# Sensors.net
KiCad netlist of a schematic drawn in Altium Designer
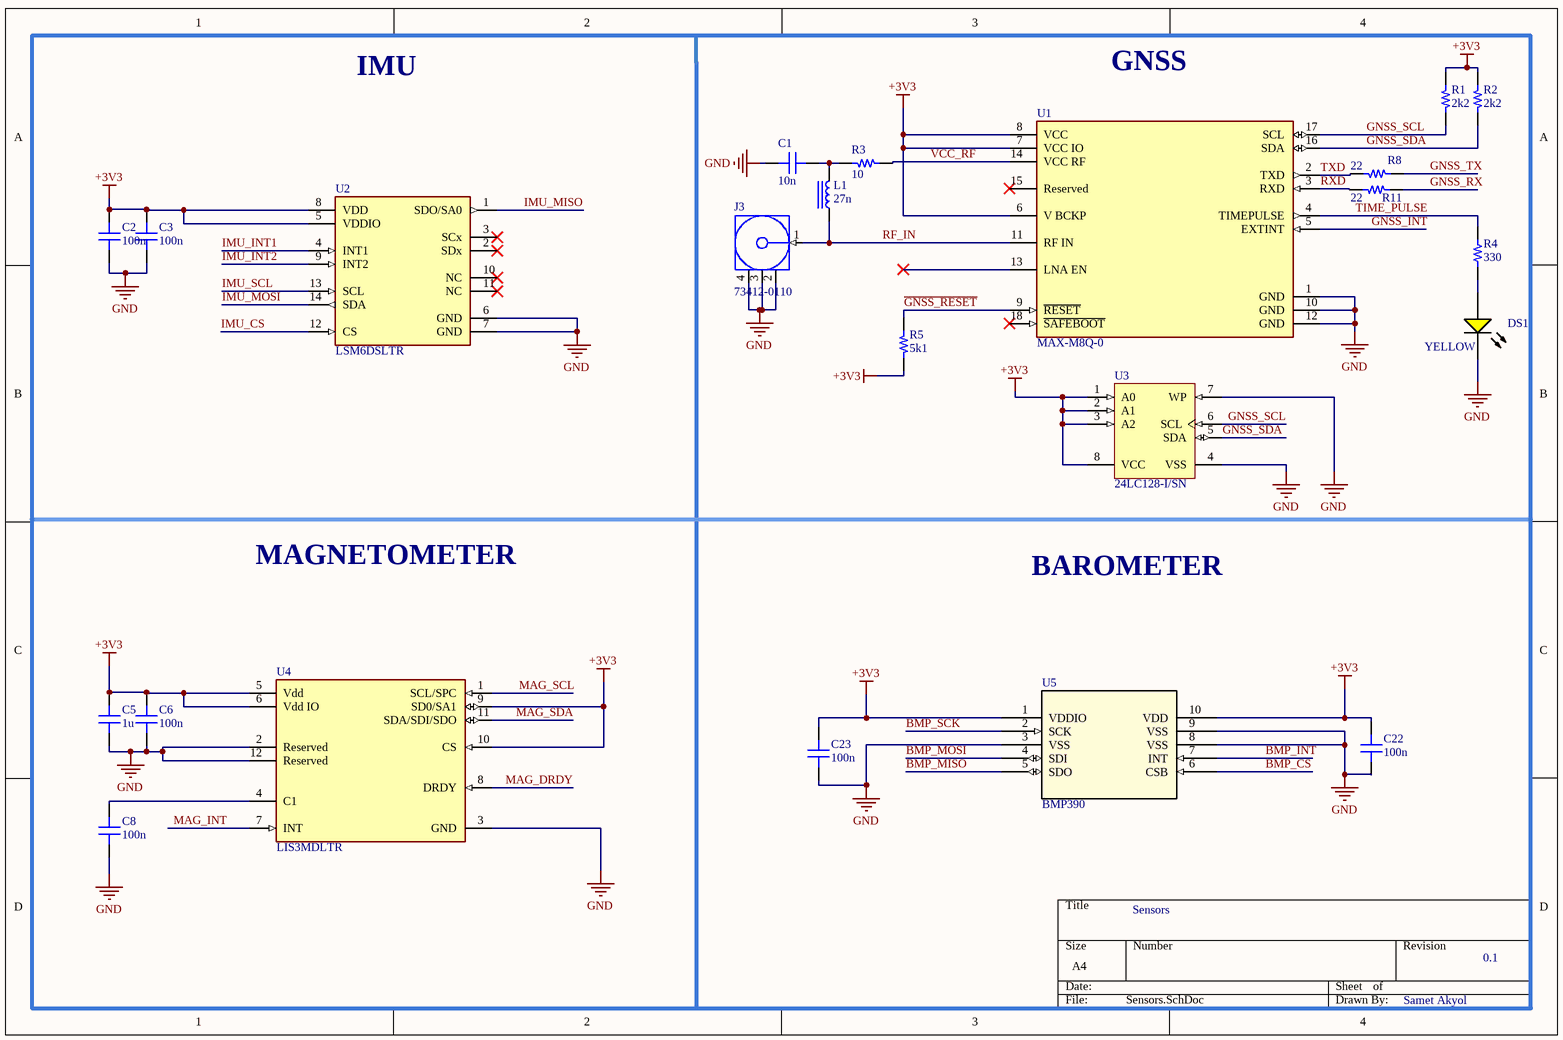
[diagram p0: Sensors.SchDoc]

(export (version "E")
  (design (tool "Eeschema 10.0.6"))
  (components
    (comp (ref "C1")
      (value "10n")
      (footprint "CAP 0402_1005")
      (description "CAP CER 150PF 50V NP0 0402")
      (fields (field (name "PART NUMBER") "C0402C151F5GAC7867") (field (name "MANUFACTURER") "KEMET"))
      (libsource (lib "Celestial Altium Library - altium_library") (part "Capacitor"))
    )
    (comp (ref "C2")
      (value "100n")
      (footprint "CAP 0402_1005")
      (description "CAP CER 0.1UF 10V X7R 0402")
      (fields
        (field (name "PART NUMBER") "MD0402BB104K100NGHT-EM")
        (field (name "MANUFACTURER") "Knowles Novacap")
      )
      (libsource (lib "Celestial Altium Library - altium_library") (part "Capacitor"))
    )
    (comp (ref "C3")
      (value "100n")
      (footprint "CAP 0402_1005")
      (description "CAP CER 0.1UF 10V X7R 0402")
      (fields
        (field (name "PART NUMBER") "MD0402BB104K100NGHT-EM")
        (field (name "MANUFACTURER") "Knowles Novacap")
      )
      (libsource (lib "Celestial Altium Library - altium_library") (part "Capacitor"))
    )
    (comp (ref "C5")
      (value "1u")
      (footprint "CAP 0402_1005")
      (description "CAP CER 0.1UF 10V X7R 0402")
      (fields
        (field (name "PART NUMBER") "MD0402BB104K100NGHT-EM")
        (field (name "MANUFACTURER") "Knowles Novacap")
      )
      (libsource (lib "Celestial Altium Library - altium_library") (part "Capacitor"))
    )
    (comp (ref "C6")
      (value "100n")
      (footprint "CAP 0402_1005")
      (description "CAP CER 0.1UF 10V X7R 0402")
      (fields
        (field (name "PART NUMBER") "MD0402BB104K100NGHT-EM")
        (field (name "MANUFACTURER") "Knowles Novacap")
      )
      (libsource (lib "Celestial Altium Library - altium_library") (part "Capacitor"))
    )
    (comp (ref "C8")
      (value "100n")
      (footprint "CAP 0402_1005")
      (description "CAP CER 0.1UF 10V X7R 0402")
      (fields
        (field (name "PART NUMBER") "MD0402BB104K100NGHT-EM")
        (field (name "MANUFACTURER") "Knowles Novacap")
      )
      (libsource (lib "Celestial Altium Library - altium_library") (part "Capacitor"))
    )
    (comp (ref "C22")
      (value "100n")
      (footprint "CAP 0402_1005")
      (description "CAP CER 0.1UF 10V X7R 0402")
      (fields
        (field (name "PART NUMBER") "MD0402BB104K100NGHT-EM")
        (field (name "MANUFACTURER") "Knowles Novacap")
      )
      (libsource (lib "Celestial Altium Library - altium_library") (part "Capacitor"))
    )
    (comp (ref "C23")
      (value "100n")
      (footprint "CAP 0402_1005")
      (description "CAP CER 0.1UF 10V X7R 0402")
      (fields
        (field (name "PART NUMBER") "MD0402BB104K100NGHT-EM")
        (field (name "MANUFACTURER") "Knowles Novacap")
      )
      (libsource (lib "Celestial Altium Library - altium_library") (part "Capacitor"))
    )
    (comp (ref "DS1")
      (value "YELLOW")
      (footprint "VISH-TLMY1000_V")
      (description "Low Current LED, 40 mW, -40 to 100 degC, 2-Pin SMD, RoHS, Tape and Reel")
      (fields (field (name "MANUFACTURER") "Vishay"))
      (libsource (lib "Altium Content Vault") (part "LED-YELLOW-AK-2"))
    )
    (comp (ref "J3")
      (value "73412-0110")
      (footprint "MOLX-73412-0110_V")
      (description "MCRF, PCB Vertical Jack Receptacle, 50 Ohm, 4-Pin SMD, RoHS, Tape and Reel")
      (libsource (lib "Altium Content Vault") (part "MOLX-73412-0110"))
    )
    (comp (ref "L1")
      (value "27n")
      (footprint "IND 0402_1005 RF WW")
      (description "FIXED IND 160NH 480MA 0.33OHM SM")
      (fields
        (field (name "PART NUMBER") "LQW15CNR16J00D")
        (field (name "MANUFACTURER") "Murata Electronics")
      )
      (libsource (lib "Celestial Altium Library - altium_library") (part "Inductor"))
    )
    (comp (ref "R1")
      (value "2k2")
      (footprint "RES 0402_1005")
      (description "RES 249K OHM 0.1% 1/10W 0402")
      (fields
        (field (name "PART NUMBER") "RP73PF1E249KBTD")
        (field (name "MANUFACTURER") "TE Connectivity Passive Product")
      )
      (libsource (lib "Celestial Altium Library - altium_library") (part "Resistor"))
    )
    (comp (ref "R2")
      (value "2k2")
      (footprint "RES 0402_1005")
      (description "RES 249K OHM 0.1% 1/10W 0402")
      (fields
        (field (name "PART NUMBER") "RP73PF1E249KBTD")
        (field (name "MANUFACTURER") "TE Connectivity Passive Product")
      )
      (libsource (lib "Celestial Altium Library - altium_library") (part "Resistor"))
    )
    (comp (ref "R3")
      (value "10")
      (footprint "RES 0402_1005")
      (description "RES 249K OHM 0.1% 1/10W 0402")
      (fields
        (field (name "PART NUMBER") "RP73PF1E249KBTD")
        (field (name "MANUFACTURER") "TE Connectivity Passive Product")
      )
      (libsource (lib "Celestial Altium Library - altium_library") (part "Resistor"))
    )
    (comp (ref "R4")
      (value "330")
      (footprint "RES 0603_1608")
      (description "RES SMD 330 OHM 1% 1/5W 0603")
      (fields
        (field (name "PART NUMBER") "CRGH0603F330R")
        (field (name "MANUFACTURER") "TE Connectivity Passive Product")
      )
      (libsource (lib "Celestial Altium Library - altium_library") (part "Resistor"))
    )
    (comp (ref "R5")
      (value "5k1")
      (footprint "RES 0402_1005")
      (description "RES 249K OHM 0.1% 1/10W 0402")
      (fields
        (field (name "PART NUMBER") "RP73PF1E249KBTD")
        (field (name "MANUFACTURER") "TE Connectivity Passive Product")
      )
      (libsource (lib "Celestial Altium Library - altium_library") (part "Resistor"))
    )
    (comp (ref "R8")
      (value "22")
      (footprint "RES 0402_1005")
      (description "RES 249K OHM 0.1% 1/10W 0402")
      (fields
        (field (name "PART NUMBER") "RP73PF1E249KBTD")
        (field (name "MANUFACTURER") "TE Connectivity Passive Product")
      )
      (libsource (lib "Celestial Altium Library - altium_library") (part "Resistor"))
    )
    (comp (ref "R11")
      (value "22")
      (footprint "RES 0402_1005")
      (description "RES 249K OHM 0.1% 1/10W 0402")
      (fields
        (field (name "PART NUMBER") "RP73PF1E249KBTD")
        (field (name "MANUFACTURER") "TE Connectivity Passive Product")
      )
      (libsource (lib "Celestial Altium Library - altium_library") (part "Resistor"))
    )
    (comp (ref "U1")
      (value "MAX-M8Q-0")
      (footprint "FP-MAX-M8Q-0-MFG")
      (description "RF RCVR GNSS/GPS 1.575GHZ 18LCC")
      (libsource (lib "Altium Content Vault") (part "3a4eaf80b39255b10f8ea21395ff7da"))
    )
    (comp (ref "U2")
      (value "LSM6DSLTR")
      (footprint "FP-LGA-14L-DM00249496-MFG")
      (description "IMU ACCEL/GYRO I2C/SPI 14LGA")
      (fields
        (field (name "MANUFACTURER") "STMicroelectronics")
        (field (name "OCTOPART") "https://octopart.com/lsm6dsltr-stmicroelectronics-66358193")
      )
      (libsource (lib "Altium Content Vault") (part "4e27e7d1829efda5344af1708d65448"))
    )
    (comp (ref "U3")
      (value "24LC128-I/SN")
      (footprint "SOIC-SN8_M")
      (description "128Kbit, 400kHz, 2.5V, I2C Serial EEPROM, 8-Pin SOIC 150mil, Industrial Temperature")
      (libsource (lib "Altium Content Vault") (part "MEM-SEEPROM-34AA02-IL8"))
    )
    (comp (ref "U4")
      (value "LIS3MDLTR")
      (footprint "FP-VFLGA-12-8365767-MFG")
      (description "SENSOR MR I2C/SPI 12LGA")
      (fields
        (field (name "OCTOPART") "https://octopart.com/lis3mdltr-stmicroelectronics-29403125")
        (field (name "MANUFACTURER") "STMicroelectronics")
      )
      (libsource (lib "Altium Content Vault") (part "41c0331d4207a07573b21020ef49d7d"))
    )
    (comp (ref "U5")
      (value "BMP390")
      (footprint "10LGA_2X2X0p75_BOS-L")
      (description "No Description Available")
      (libsource (lib "BMP390") (part "BMP390"))
    )
  )
  (nets
    (net (code "1") (name "+3V3") (class "Default")
      (node (ref "C2") (pin "2") (pinfunction "2_2") (pintype "passive"))
      (node (ref "C22") (pin "2") (pinfunction "2_2") (pintype "passive"))
      (node (ref "C23") (pin "2") (pinfunction "2_2") (pintype "passive"))
      (node (ref "C3") (pin "2") (pinfunction "2_2") (pintype "passive"))
      (node (ref "C5") (pin "2") (pinfunction "2_2") (pintype "passive"))
      (node (ref "C6") (pin "2") (pinfunction "2_2") (pintype "passive"))
      (node (ref "R1") (pin "2") (pinfunction "2_2") (pintype "passive"))
      (node (ref "R2") (pin "2") (pinfunction "2_2") (pintype "passive"))
      (node (ref "R5") (pin "1") (pinfunction "1_1") (pintype "passive"))
      (node (ref "U1") (pin "6") (pinfunction "V_BCKP_6") (pintype "power_in"))
      (node (ref "U1") (pin "7") (pinfunction "VCC_IO_7") (pintype "power_in"))
      (node (ref "U1") (pin "8") (pinfunction "VCC_8") (pintype "power_in"))
      (node (ref "U2") (pin "5") (pinfunction "VDDIO_5") (pintype "power_in"))
      (node (ref "U2") (pin "8") (pinfunction "VDD_8") (pintype "power_in"))
      (node (ref "U3") (pin "1") (pinfunction "A0_1") (pintype "input"))
      (node (ref "U3") (pin "2") (pinfunction "A1_2") (pintype "input"))
      (node (ref "U3") (pin "3") (pinfunction "A2_3") (pintype "input"))
      (node (ref "U3") (pin "8") (pinfunction "VCC_8") (pintype "power_in"))
      (node (ref "U4") (pin "10") (pinfunction "CS_10") (pintype "input"))
      (node (ref "U4") (pin "5") (pinfunction "Vdd_5") (pintype "power_in"))
      (node (ref "U4") (pin "6") (pinfunction "Vdd_IO_6") (pintype "power_in"))
      (node (ref "U4") (pin "9") (pinfunction "SD0/SA1_9") (pintype "bidirectional"))
      (node (ref "U5") (pin "1") (pinfunction "VDDIO_1") (pintype "power_in"))
      (node (ref "U5") (pin "10") (pinfunction "VDD_10") (pintype "power_in"))
    )
    (net (code "2") (name "/BMP_CS") (class "Default")
      (node (ref "U5") (pin "6") (pinfunction "CSB_6") (pintype "input"))
    )
    (net (code "3") (name "/BMP_INT") (class "Default")
      (node (ref "U5") (pin "7") (pinfunction "INT_7") (pintype "input"))
    )
    (net (code "4") (name "/BMP_MISO") (class "Default")
      (node (ref "U5") (pin "5") (pinfunction "SDO_5") (pintype "bidirectional"))
    )
    (net (code "5") (name "/BMP_MOSI") (class "Default")
      (node (ref "U5") (pin "4") (pinfunction "SDI_4") (pintype "bidirectional"))
    )
    (net (code "6") (name "/BMP_SCK") (class "Default")
      (node (ref "U5") (pin "2") (pinfunction "SCK_2") (pintype "input"))
    )
    (net (code "7") (name "/GNSS_INT") (class "Default")
      (node (ref "U1") (pin "5") (pinfunction "EXTINT_5") (pintype "input"))
    )
    (net (code "8") (name "/GNSS_RX") (class "Default")
      (node (ref "R11") (pin "1") (pinfunction "1_1") (pintype "passive"))
    )
    (net (code "9") (name "/GNSS_SCL") (class "Default")
      (node (ref "R1") (pin "1") (pinfunction "1_1") (pintype "passive"))
      (node (ref "U1") (pin "17") (pinfunction "SCL_17") (pintype "bidirectional"))
      (node (ref "U3") (pin "6") (pinfunction "SCL_6") (pintype "input"))
    )
    (net (code "10") (name "/GNSS_SDA") (class "Default")
      (node (ref "R2") (pin "1") (pinfunction "1_1") (pintype "passive"))
      (node (ref "U1") (pin "16") (pinfunction "SDA_16") (pintype "bidirectional"))
      (node (ref "U3") (pin "5") (pinfunction "SDA_5") (pintype "bidirectional"))
    )
    (net (code "11") (name "/GNSS_TX") (class "Default")
      (node (ref "R8") (pin "1") (pinfunction "1_1") (pintype "passive"))
    )
    (net (code "12") (name "/IMU_CS") (class "Default")
      (node (ref "U2") (pin "12") (pinfunction "CS_12") (pintype "input"))
    )
    (net (code "13") (name "/IMU_INT1") (class "Default")
      (node (ref "U2") (pin "4") (pinfunction "INT1_4") (pintype "input"))
    )
    (net (code "14") (name "/IMU_INT2") (class "Default")
      (node (ref "U2") (pin "9") (pinfunction "INT2_9") (pintype "input"))
    )
    (net (code "15") (name "/IMU_MISO") (class "Default")
      (node (ref "U2") (pin "1") (pinfunction "SDO/SA0_1") (pintype "output"))
    )
    (net (code "16") (name "/IMU_MOSI") (class "Default")
      (node (ref "U2") (pin "14") (pinfunction "SDA_14") (pintype "output"))
    )
    (net (code "17") (name "/IMU_SCL") (class "Default")
      (node (ref "U2") (pin "13") (pinfunction "SCL_13") (pintype "input"))
    )
    (net (code "18") (name "/MAG_DRDY") (class "Default")
      (node (ref "U4") (pin "8") (pinfunction "DRDY_8") (pintype "input"))
    )
    (net (code "19") (name "/MAG_INT") (class "Default")
      (node (ref "U4") (pin "7") (pinfunction "INT_7") (pintype "input"))
    )
    (net (code "20") (name "/MAG_SCL") (class "Default")
      (node (ref "U4") (pin "1") (pinfunction "SCL/SPC_1") (pintype "input"))
    )
    (net (code "21") (name "/MAG_SDA") (class "Default")
      (node (ref "U4") (pin "11") (pinfunction "SDA/SDI/SDO_11") (pintype "bidirectional"))
    )
    (net (code "22") (name "/RF_IN") (class "Default")
      (node (ref "J3") (pin "1") (pinfunction "SIGNAL_1") (pintype "input"))
      (node (ref "L1") (pin "2") (pinfunction "2_2") (pintype "passive"))
      (node (ref "U1") (pin "11") (pinfunction "RF_IN_11") (pintype "passive"))
    )
    (net (code "23") (name "/RXD") (class "Default")
      (node (ref "R11") (pin "2") (pinfunction "2_2") (pintype "passive"))
      (node (ref "U1") (pin "3") (pinfunction "RXD_3") (pintype "input"))
    )
    (net (code "24") (name "/TIME_PULSE") (class "Default")
      (node (ref "R4") (pin "2") (pinfunction "2_2") (pintype "passive"))
      (node (ref "U1") (pin "4") (pinfunction "TIMEPULSE_4") (pintype "output"))
    )
    (net (code "25") (name "/TXD") (class "Default")
      (node (ref "R8") (pin "2") (pinfunction "2_2") (pintype "passive"))
      (node (ref "U1") (pin "2") (pinfunction "TXD_2") (pintype "output"))
    )
    (net (code "26") (name "/VCC_RF") (class "Default")
      (node (ref "R3") (pin "2") (pinfunction "2_2") (pintype "passive"))
      (node (ref "U1") (pin "14") (pinfunction "VCC_RF_14") (pintype "power_in"))
    )
    (net (code "27") (name "/~{GNSS_RESET}") (class "Default")
      (node (ref "R5") (pin "2") (pinfunction "2_2") (pintype "passive"))
      (node (ref "U1") (pin "9") (pinfunction "~{RESET}_9") (pintype "input"))
    )
    (net (code "28") (name "GND") (class "Default")
      (node (ref "C1") (pin "2") (pinfunction "2_2") (pintype "passive"))
      (node (ref "C2") (pin "1") (pinfunction "1_1") (pintype "passive"))
      (node (ref "C22") (pin "1") (pinfunction "1_1") (pintype "passive"))
      (node (ref "C23") (pin "1") (pinfunction "1_1") (pintype "passive"))
      (node (ref "C3") (pin "1") (pinfunction "1_1") (pintype "passive"))
      (node (ref "C5") (pin "1") (pinfunction "1_1") (pintype "passive"))
      (node (ref "C6") (pin "1") (pinfunction "1_1") (pintype "passive"))
      (node (ref "C8") (pin "1") (pinfunction "1_1") (pintype "passive"))
      (node (ref "DS1") (pin "2") (pinfunction "K_2") (pintype "passive"))
      (node (ref "J3") (pin "2") (pinfunction "GND_2") (pintype "power_in"))
      (node (ref "J3") (pin "3") (pinfunction "GND_3") (pintype "power_in"))
      (node (ref "J3") (pin "4") (pinfunction "GND_4") (pintype "power_in"))
      (node (ref "U1") (pin "1") (pinfunction "GND_1") (pintype "power_in"))
      (node (ref "U1") (pin "10") (pinfunction "GND_10") (pintype "power_in"))
      (node (ref "U1") (pin "12") (pinfunction "GND_12") (pintype "power_in"))
      (node (ref "U2") (pin "6") (pinfunction "GND_6") (pintype "power_in"))
      (node (ref "U2") (pin "7") (pinfunction "GND_7") (pintype "power_in"))
      (node (ref "U3") (pin "4") (pinfunction "VSS_4") (pintype "power_in"))
      (node (ref "U3") (pin "7") (pinfunction "WP_7") (pintype "input"))
      (node (ref "U4") (pin "12") (pinfunction "Reserved_12") (pintype "passive"))
      (node (ref "U4") (pin "2") (pinfunction "Reserved_2") (pintype "passive"))
      (node (ref "U4") (pin "3") (pinfunction "GND_3") (pintype "power_in"))
      (node (ref "U5") (pin "3") (pinfunction "VSS_3") (pintype "power_in"))
      (node (ref "U5") (pin "8") (pinfunction "VSS_8") (pintype "power_in"))
      (node (ref "U5") (pin "9") (pinfunction "VSS_9") (pintype "power_in"))
    )
    (net (code "29") (name "Net-(C1-Pad1)") (class "Default")
      (node (ref "C1") (pin "1") (pinfunction "1_1") (pintype "passive"))
      (node (ref "L1") (pin "1") (pinfunction "1_1") (pintype "passive"))
      (node (ref "R3") (pin "1") (pinfunction "1_1") (pintype "passive"))
    )
    (net (code "30") (name "Net-(DS1-A)") (class "Default")
      (node (ref "DS1") (pin "1") (pinfunction "A_1") (pintype "passive"))
      (node (ref "R4") (pin "1") (pinfunction "1_1") (pintype "passive"))
    )
    (net (code "31") (name "Net-(U4-C1)") (class "Default")
      (node (ref "C8") (pin "2") (pinfunction "2_2") (pintype "passive"))
      (node (ref "U4") (pin "4") (pinfunction "C1_4") (pintype "passive"))
    )
    (net (code "32") (name "unconnected-(U1-LNA_EN-Pad13)") (class "Default")
      (node (ref "U1") (pin "13") (pinfunction "LNA_EN_13") (pintype "passive+no_connect"))
    )
    (net (code "33") (name "unconnected-(U1-Reserved-Pad15)") (class "Default")
      (node (ref "U1") (pin "15") (pinfunction "Reserved_15") (pintype "passive+no_connect"))
    )
    (net (code "34") (name "unconnected-(U1-~{SAFEBOOT}-Pad18)") (class "Default")
      (node (ref "U1") (pin "18") (pinfunction "~{SAFEBOOT}_18") (pintype "input+no_connect"))
    )
    (net (code "35") (name "unconnected-(U2-NC-Pad10)") (class "Default")
      (node (ref "U2") (pin "10") (pinfunction "NC_10") (pintype "passive+no_connect"))
    )
    (net (code "36") (name "unconnected-(U2-NC-Pad11)") (class "Default")
      (node (ref "U2") (pin "11") (pinfunction "NC_11") (pintype "passive+no_connect"))
    )
    (net (code "37") (name "unconnected-(U2-SCx-Pad3)") (class "Default")
      (node (ref "U2") (pin "3") (pinfunction "SCx_3") (pintype "passive+no_connect"))
    )
    (net (code "38") (name "unconnected-(U2-SDx-Pad2)") (class "Default")
      (node (ref "U2") (pin "2") (pinfunction "SDx_2") (pintype "passive+no_connect"))
    )
  )
)
